# 1-RF-S.net
KiCad netlist of a schematic drawn in Altium Designer
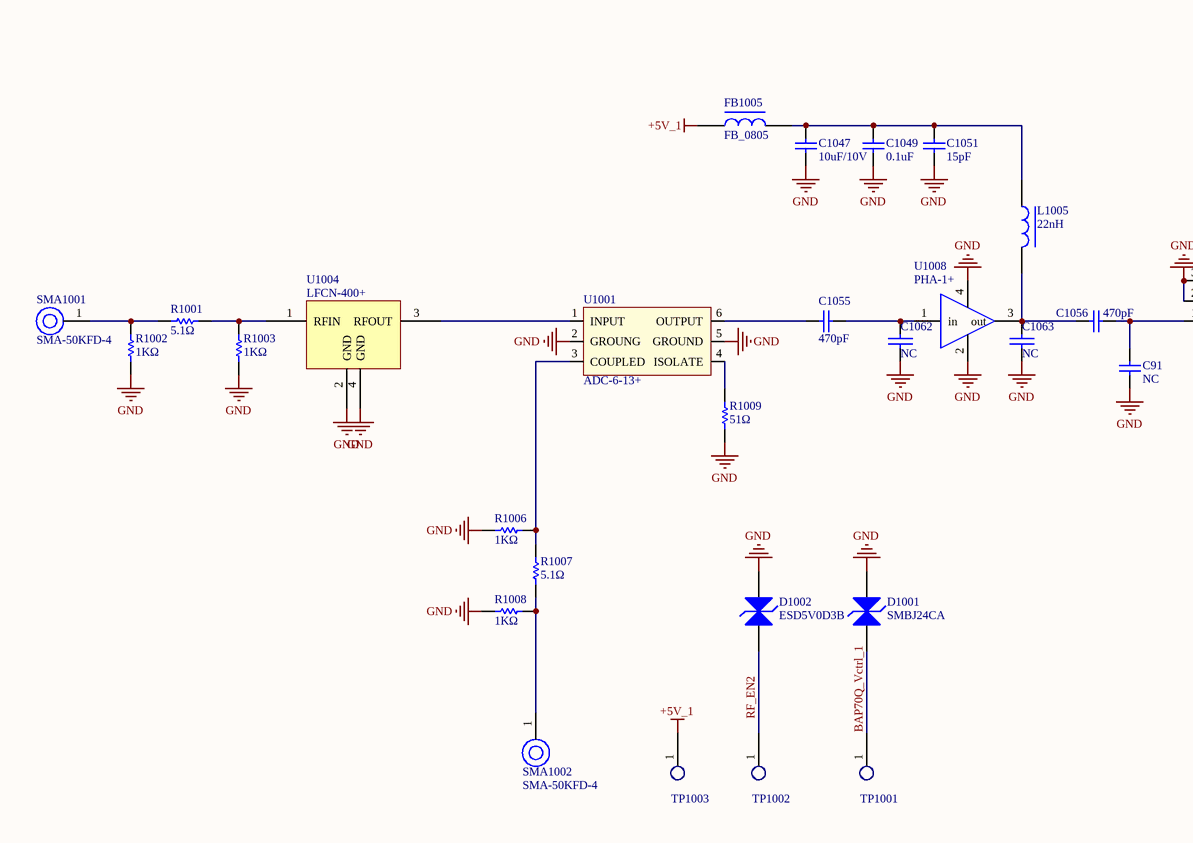
[diagram p0: 1-RF-S.SchDoc, left]
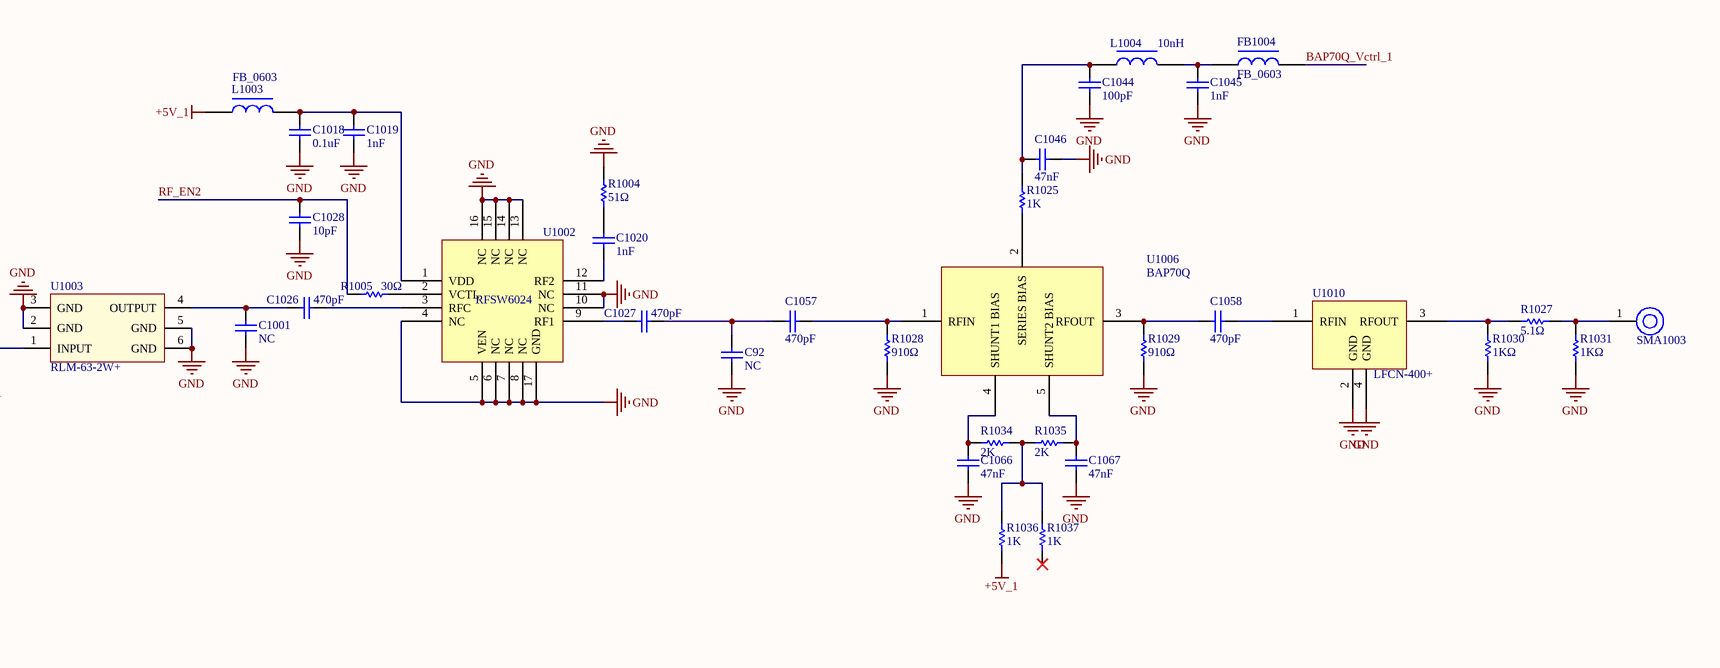
[diagram p1: 1-RF-S.SchDoc, right]

(export (version "E")
  (design (tool "Eeschema 10.0.6"))
  (components
    (comp (ref "C91")
      (value "NC")
      (footprint "C0805")
      (description "贴片电容_GRM215C1H100JA01D_10pF±5%,50V,0805")
      (libsource (lib "21贴片电容0805") (part "10pF贴片电容"))
    )
    (comp (ref "C92")
      (value "NC")
      (footprint "C0805")
      (description "贴片电容_GRM215C1H100JA01D_10pF±5%,50V,0805")
      (libsource (lib "21贴片电容0805") (part "10pF贴片电容"))
    )
    (comp (ref "C1001")
      (value "NC")
      (footprint "C0805")
      (description "贴片电容_GRM215C1H100JA01D_10pF±5%,50V,0805")
      (libsource (lib "21贴片电容0805") (part "10pF贴片电容"))
    )
    (comp (ref "C1018")
      (value "0.1uF")
      (footprint "C0603")
      (description "贴片电容_GRM188R71H104KA01D_0.1uF±10%,50V,0603")
      (libsource (lib "20贴片电容0603") (part "0.1uF贴片电容"))
    )
    (comp (ref "C1019")
      (value "1nF")
      (footprint "C0603")
      (description "贴片电容_GRM188R71H102KA01_1000pF±10%,50V,0603")
      (libsource (lib "20贴片电容0603") (part "1000pF贴片电容"))
    )
    (comp (ref "C1020")
      (value "1nF")
      (footprint "C0603")
      (description "贴片电容_GRM188R71H102KA01_1000pF±10%,50V,0603")
      (libsource (lib "20贴片电容0603") (part "1000pF贴片电容"))
    )
    (comp (ref "C1026")
      (value "470pF")
      (footprint "C0805")
      (description "贴片电容_GRM215C1H100JA01D_10pF±5%,50V,0805")
      (libsource (lib "21贴片电容0805") (part "10pF贴片电容"))
    )
    (comp (ref "C1027")
      (value "470pF")
      (footprint "C0805")
      (description "贴片电容_GRM215C1H100JA01D_10pF±5%,50V,0805")
      (libsource (lib "21贴片电容0805") (part "10pF贴片电容"))
    )
    (comp (ref "C1028")
      (value "10pF")
      (footprint "C0603")
      (description "贴片电容_0603CG100J500NT_10pF±5%,50V,0603")
      (libsource (lib "20贴片电容0603") (part "10pF贴片电容"))
    )
    (comp (ref "C1044")
      (value "100pF")
      (footprint "C0603")
      (description "贴片电容_GRM185C1H101K_100pF±10%,50V,0603")
      (libsource (lib "20贴片电容0603") (part "100pF贴片电容"))
    )
    (comp (ref "C1045")
      (value "1nF")
      (footprint "C0603")
      (description "贴片电容_GRM185C1H101K_100pF±10%,50V,0603")
      (libsource (lib "20贴片电容0603") (part "100pF贴片电容"))
    )
    (comp (ref "C1046")
      (value "47nF")
      (footprint "C0603")
      (description "贴片电容_GRM1885C1H473KA01D_47nF±10 %,50V,0603")
      (libsource (lib "20贴片电容0603") (part "47nF贴片电容"))
    )
    (comp (ref "C1047")
      (value "10uF/10V")
      (footprint "C0805")
      (description "贴片电容_GRM21BR61A106KE19L_10uF±10%,10V,0805")
      (libsource (lib "21贴片电容0805") (part "10uF贴片电容"))
    )
    (comp (ref "C1049")
      (value "0.1uF")
      (footprint "C0805")
      (description "贴片电容_GRM21BR71E104KA01L_100nF±10%,25V,0805")
      (libsource (lib "21贴片电容0805") (part "100nF贴片电容"))
    )
    (comp (ref "C1051")
      (value "15pF")
      (footprint "C0805")
      (description "贴片电容_GRM2165C1H150JA01D_15pF±5%,50V,0805")
      (libsource (lib "21贴片电容0805") (part "15pF贴片电容"))
    )
    (comp (ref "C1055")
      (value "470pF")
      (footprint "C0805")
      (description "贴片电容_GRM2165C1H1R0CA01D_1pF±0.25F,50V,0805")
      (libsource (lib "21贴片电容0805") (part "1pF贴片电容"))
    )
    (comp (ref "C1056")
      (value "470pF")
      (footprint "C0805")
      (description "贴片电容_GRM2165C1H3R0DD47D_3pF±0.5pF%,50V,0805")
      (libsource (lib "21贴片电容0805") (part "3pF贴片电容"))
    )
    (comp (ref "C1057")
      (value "470pF")
      (footprint "C0805")
      (description "贴片电容_GRM2165C1H101JA01D_100pF±5%,50V,0805")
      (libsource (lib "21贴片电容0805") (part "100pF贴片电容"))
    )
    (comp (ref "C1058")
      (value "470pF")
      (footprint "C0805")
      (description "贴片电容_GRM2165C1H101JA01D_100pF±5%,50V,0805")
      (libsource (lib "21贴片电容0805") (part "100pF贴片电容"))
    )
    (comp (ref "C1062")
      (value "NC")
      (footprint "C0805")
      (description "普通电容")
      (libsource (lib "27贴片电容DLC10D-0805") (part "DLC_0.5pF"))
    )
    (comp (ref "C1063")
      (value "NC")
      (footprint "C0805")
      (description "普通电容")
      (libsource (lib "27贴片电容DLC10D-0805") (part "DLC_0.5pF"))
    )
    (comp (ref "C1066")
      (value "47nF")
      (footprint "C0603")
      (description "贴片电容_GRM1885C1H473KA01D_47nF±10 %,50V,0603")
      (libsource (lib "20贴片电容0603") (part "47nF贴片电容"))
    )
    (comp (ref "C1067")
      (value "47nF")
      (footprint "C0603")
      (description "贴片电容_GRM1885C1H473KA01D_47nF±10 %,50V,0603")
      (libsource (lib "20贴片电容0603") (part "47nF贴片电容"))
    )
    (comp (ref "D1001")
      (value "SMBJ24CA")
      (footprint "DO-214AA")
      (description "TVS_SMBJ24CA_SMB封装")
      (libsource (lib "40二极管") (part "SMBJ12CA"))
    )
    (comp (ref "D1002")
      (value "ESD5V0D3B")
      (footprint "SOD-323")
      (description "ESD_ESD5V0D3B_SOD-323,5V,双管")
      (libsource (lib "40二极管") (part "ESD5B5.0ST1G"))
    )
    (comp (ref "FB1004")
      (value "FB_0603")
      (footprint "L0603")
      (description "贴片磁珠_100R,0603")
      (libsource (lib "32贴片磁珠0603") (part "0603贴片磁珠"))
    )
    (comp (ref "FB1005")
      (value "FB_0805")
      (footprint "L0805")
      (description "贴片磁珠_600R,0805")
      (libsource (lib "33贴片磁珠0805") (part "0805贴片磁珠"))
    )
    (comp (ref "L1003")
      (value "FB_0603")
      (footprint "L0603")
      (libsource (lib "33贴片磁珠0805") (part "0805贴片磁珠"))
    )
    (comp (ref "L1004")
      (value "10nH")
      (footprint "L0603")
      (description "贴片电感_3.3nH,0603")
      (libsource (lib "30贴片电感0603") (part "3.3nH贴片电感"))
    )
    (comp (ref "L1005")
      (value "22nH")
      (footprint "L0805")
      (description "贴片电感_22nH,0805")
      (libsource (lib "31贴片电感0805") (part "22nH贴片电感"))
    )
    (comp (ref "R1001")
      (value "5.1Ω")
      (footprint "R0805")
      (description "贴片电阻_0805,5.1Ω,±1％")
      (libsource (lib "11贴片电阻0805") (part "18Ω贴片电阻"))
    )
    (comp (ref "R1002")
      (value "1KΩ")
      (footprint "R0805")
      (description "贴片电阻_0805,1KΩ,±5％")
      (libsource (lib "11贴片电阻0805") (part "300Ω贴片电阻"))
    )
    (comp (ref "R1003")
      (value "1KΩ")
      (footprint "R0805")
      (description "贴片电阻_0805,1KΩ,±5％")
      (libsource (lib "11贴片电阻0805") (part "300Ω贴片电阻"))
    )
    (comp (ref "R1004")
      (value "51Ω")
      (footprint "R0603")
      (description "贴片电阻_51Ω±5%,0603")
      (libsource (lib "10贴片电阻0603") (part "51Ω贴片电阻"))
    )
    (comp (ref "R1005")
      (value "30Ω")
      (footprint "R0603")
      (description "贴片电阻_30Ω±5%,0603")
      (libsource (lib "10贴片电阻0603") (part "30Ω贴片电阻"))
    )
    (comp (ref "R1006")
      (value "1KΩ")
      (footprint "R0805")
      (description "贴片电阻_0805,1KΩ,±5％")
      (libsource (lib "11贴片电阻0805") (part "300Ω贴片电阻"))
    )
    (comp (ref "R1007")
      (value "5.1Ω")
      (footprint "R0805")
      (description "贴片电阻_0805,5.1Ω,±1％")
      (libsource (lib "11贴片电阻0805") (part "18Ω贴片电阻"))
    )
    (comp (ref "R1008")
      (value "1KΩ")
      (footprint "R0805")
      (description "贴片电阻_0805,1KΩ,±5％")
      (libsource (lib "11贴片电阻0805") (part "300Ω贴片电阻"))
    )
    (comp (ref "R1009")
      (value "51Ω")
      (footprint "R0805")
      (description "贴片电阻_51Ω±5%,0805")
      (libsource (lib "11贴片电阻0805") (part "51Ω贴片电阻"))
    )
    (comp (ref "R1025")
      (value "1K")
      (footprint "R0603")
      (description "贴片电阻_1K±5%,0603")
      (libsource (lib "10贴片电阻0603") (part "1K贴片电阻"))
    )
    (comp (ref "R1027")
      (value "5.1Ω")
      (footprint "R0805")
      (description "贴片电阻_0805,5.1Ω,±1％")
      (libsource (lib "11贴片电阻0805") (part "18Ω贴片电阻"))
    )
    (comp (ref "R1028")
      (value "910Ω")
      (footprint "R0805")
      (description "贴片电阻_910Ω±5%,0805")
      (libsource (lib "11贴片电阻0805") (part "910Ω贴片电阻"))
    )
    (comp (ref "R1029")
      (value "910Ω")
      (footprint "R0805")
      (description "贴片电阻_910Ω±5%,0805")
      (libsource (lib "11贴片电阻0805") (part "910Ω贴片电阻"))
    )
    (comp (ref "R1030")
      (value "1KΩ")
      (footprint "R0805")
      (description "贴片电阻_0805,1KΩ,±5％")
      (libsource (lib "11贴片电阻0805") (part "300Ω贴片电阻"))
    )
    (comp (ref "R1031")
      (value "1KΩ")
      (footprint "R0805")
      (description "贴片电阻_0805,1KΩ,±5％")
      (libsource (lib "11贴片电阻0805") (part "300Ω贴片电阻"))
    )
    (comp (ref "R1034")
      (value "2K")
      (footprint "R0603")
      (description "贴片电阻_2K±5%,0603")
      (libsource (lib "10贴片电阻0603") (part "2K贴片电阻"))
    )
    (comp (ref "R1035")
      (value "2K")
      (footprint "R0603")
      (description "贴片电阻_2K±5%,0603")
      (libsource (lib "10贴片电阻0603") (part "2K贴片电阻"))
    )
    (comp (ref "R1036")
      (value "1K")
      (footprint "R0603")
      (description "贴片电阻_1K±5%,0603")
      (libsource (lib "10贴片电阻0603") (part "1K贴片电阻"))
    )
    (comp (ref "R1037")
      (value "1K")
      (footprint "R0603")
      (description "贴片电阻_1K±5%,0603")
      (libsource (lib "10贴片电阻0603") (part "1K贴片电阻"))
    )
    (comp (ref "SMA1001")
      (value "SMA-50KFD-4")
      (footprint "SMA-50KFD-4")
      (description "射频同轴连接器_SMA-50KFD-4")
      (libsource (lib "90RF连接器") (part "SMA-50KFD-4"))
    )
    (comp (ref "SMA1002")
      (value "SMA-50KFD-4")
      (footprint "SMA-50KFD-4")
      (description "射频同轴连接器_SMA-50KFD-4")
      (libsource (lib "90RF连接器") (part "SMA-50KFD-4"))
    )
    (comp (ref "SMA1003")
      (value "SMA-50KFD-4")
      (footprint "SMA-50KFD-4")
      (description "射频同轴连接器_SMA-50KFD-4")
      (libsource (lib "90RF连接器") (part "SMA-50KFD-4"))
    )
    (comp (ref "TP1001")
      (value "TEST")
      (footprint "FC-M4")
      (description "表贴测试点1mm")
      (libsource (lib "92-其他（穿心电容，test等）") (part "TP1mm"))
    )
    (comp (ref "TP1002")
      (value "TEST")
      (footprint "FC-M4")
      (description "表贴测试点1mm")
      (libsource (lib "92-其他（穿心电容，test等）") (part "TP1mm"))
    )
    (comp (ref "TP1003")
      (value "TEST")
      (footprint "FC-M4")
      (description "表贴测试点1mm")
      (libsource (lib "92-其他（穿心电容，test等）") (part "TP1mm"))
    )
    (comp (ref "U1001")
      (value "ADC-6-13+")
      (footprint "6SM-2R54-7R87X5R59")
      (description "50Ω,5 to200MHz")
      (libsource (lib "105电桥&耦合器") (part "ADC-6-1R+"))
    )
    (comp (ref "U1002")
      (value "RFSW6024")
      (footprint "QFN16_0R65_4X4-1")
      (libsource (lib "80射频开关") (part "RFSW6124"))
    )
    (comp (ref "U1003")
      (value "RLM-63-2W+")
      (footprint "6SM-2R54-7R87X6R35")
      (description "50Ω,30 to6000MHz")
      (libsource (lib "106限幅器") (part "RLM-63-2W+"))
    )
    (comp (ref "U1004")
      (value "LFCN-400+")
      (footprint "LFCN-3216")
      (description "滤波器_LFCN-2500+_DC~2500MHz,3216")
      (libsource (lib "36滤波器") (part "LFCN-2500+"))
    )
    (comp (ref "U1006")
      (value "BAP70Q")
      (footprint "SOT23-5")
      (description "二极管衰减器_BAP70Q_300kHz ~4GHz,SOT753")
      (libsource (lib "75衰减器") (part "BAP70Q"))
    )
    (comp (ref "U1008")
      (value "PHA-1+")
      (footprint "SOT-89")
      (description "功率放大管_PHA-1+_0.05-6GHz,SOT89")
      (libsource (lib "73功率放大器") (part "PHA-1+"))
    )
    (comp (ref "U1010")
      (value "LFCN-400+")
      (footprint "LFCN-3216")
      (description "滤波器_LFCN-2500+_DC~2500MHz,3216")
      (libsource (lib "36滤波器") (part "LFCN-2500+"))
    )
  )
  (nets
    (net (code "1") (name "+5V_1") (class "Default")
      (node (ref "FB1005") (pin "1") (pinfunction "1_1") (pintype "passive"))
      (node (ref "L1003") (pin "1") (pinfunction "1_1") (pintype "passive"))
      (node (ref "R1036") (pin "1") (pinfunction "1_1") (pintype "passive"))
      (node (ref "TP1003") (pin "1") (pinfunction "TP_1") (pintype "passive"))
    )
    (net (code "2") (name "/BAP70Q_Vctrl_1") (class "Default")
      (node (ref "D1001") (pin "2") (pinfunction "2_2") (pintype "passive"))
      (node (ref "FB1004") (pin "2") (pinfunction "2_2") (pintype "passive"))
      (node (ref "TP1001") (pin "1") (pinfunction "TP_1") (pintype "passive"))
    )
    (net (code "3") (name "/RF_EN2") (class "Default")
      (node (ref "C1028") (pin "2") (pinfunction "2_2") (pintype "passive"))
      (node (ref "D1002") (pin "1") (pinfunction "1_1") (pintype "passive"))
      (node (ref "R1005") (pin "1") (pinfunction "1_1") (pintype "passive"))
      (node (ref "TP1002") (pin "1") (pinfunction "TP_1") (pintype "passive"))
    )
    (net (code "4") (name "GND") (class "Default")
      (node (ref "C1001") (pin "2") (pinfunction "2_2") (pintype "passive"))
      (node (ref "C1018") (pin "2") (pinfunction "2_2") (pintype "passive"))
      (node (ref "C1019") (pin "1") (pinfunction "1_1") (pintype "passive"))
      (node (ref "C1028") (pin "1") (pinfunction "1_1") (pintype "passive"))
      (node (ref "C1044") (pin "1") (pinfunction "1_1") (pintype "passive"))
      (node (ref "C1045") (pin "1") (pinfunction "1_1") (pintype "passive"))
      (node (ref "C1046") (pin "1") (pinfunction "1_1") (pintype "passive"))
      (node (ref "C1047") (pin "1") (pinfunction "1_1") (pintype "passive"))
      (node (ref "C1049") (pin "1") (pinfunction "1_1") (pintype "passive"))
      (node (ref "C1051") (pin "1") (pinfunction "1_1") (pintype "passive"))
      (node (ref "C1062") (pin "1") (pintype "passive"))
      (node (ref "C1063") (pin "1") (pintype "passive"))
      (node (ref "C1066") (pin "1") (pinfunction "1_1") (pintype "passive"))
      (node (ref "C1067") (pin "1") (pinfunction "1_1") (pintype "passive"))
      (node (ref "C91") (pin "2") (pinfunction "2_2") (pintype "passive"))
      (node (ref "C92") (pin "1") (pinfunction "1_1") (pintype "passive"))
      (node (ref "D1001") (pin "1") (pinfunction "1_1") (pintype "passive"))
      (node (ref "D1002") (pin "2") (pinfunction "2_2") (pintype "passive"))
      (node (ref "R1002") (pin "1") (pinfunction "1_1") (pintype "passive"))
      (node (ref "R1003") (pin "1") (pinfunction "1_1") (pintype "passive"))
      (node (ref "R1004") (pin "2") (pinfunction "2_2") (pintype "passive"))
      (node (ref "R1006") (pin "1") (pinfunction "1_1") (pintype "passive"))
      (node (ref "R1008") (pin "1") (pinfunction "1_1") (pintype "passive"))
      (node (ref "R1009") (pin "2") (pinfunction "2_2") (pintype "passive"))
      (node (ref "R1028") (pin "1") (pinfunction "1_1") (pintype "passive"))
      (node (ref "R1029") (pin "1") (pinfunction "1_1") (pintype "passive"))
      (node (ref "R1030") (pin "1") (pinfunction "1_1") (pintype "passive"))
      (node (ref "R1031") (pin "1") (pinfunction "1_1") (pintype "passive"))
      (node (ref "U1001") (pin "2") (pinfunction "GROUNG_2") (pintype "passive"))
      (node (ref "U1001") (pin "5") (pinfunction "GROUND_5") (pintype "passive"))
      (node (ref "U1002") (pin "10") (pinfunction "NC_10") (pintype "passive"))
      (node (ref "U1002") (pin "11") (pinfunction "NC_11") (pintype "passive"))
      (node (ref "U1002") (pin "13") (pinfunction "NC_13") (pintype "passive"))
      (node (ref "U1002") (pin "14") (pinfunction "NC_14") (pintype "passive"))
      (node (ref "U1002") (pin "15") (pinfunction "NC_15") (pintype "passive"))
      (node (ref "U1002") (pin "16") (pinfunction "NC_16") (pintype "passive"))
      (node (ref "U1002") (pin "17") (pinfunction "GND_17") (pintype "passive"))
      (node (ref "U1002") (pin "4") (pinfunction "NC_4") (pintype "passive"))
      (node (ref "U1002") (pin "5") (pinfunction "VEN_5") (pintype "passive"))
      (node (ref "U1002") (pin "6") (pinfunction "NC_6") (pintype "passive"))
      (node (ref "U1002") (pin "7") (pinfunction "NC_7") (pintype "passive"))
      (node (ref "U1002") (pin "8") (pinfunction "NC_8") (pintype "passive"))
      (node (ref "U1003") (pin "2") (pinfunction "GND_2") (pintype "passive"))
      (node (ref "U1003") (pin "3") (pinfunction "GND_3") (pintype "passive"))
      (node (ref "U1003") (pin "5") (pinfunction "GND_5") (pintype "passive"))
      (node (ref "U1003") (pin "6") (pinfunction "GND_6") (pintype "passive"))
      (node (ref "U1004") (pin "2") (pinfunction "GND_2") (pintype "passive"))
      (node (ref "U1004") (pin "4") (pinfunction "GND_4") (pintype "passive"))
      (node (ref "U1008") (pin "2") (pinfunction "2_2") (pintype "passive"))
      (node (ref "U1008") (pin "4") (pinfunction "4_4") (pintype "passive"))
      (node (ref "U1010") (pin "2") (pinfunction "GND_2") (pintype "passive"))
      (node (ref "U1010") (pin "4") (pinfunction "GND_4") (pintype "passive"))
    )
    (net (code "5") (name "Net-(C1020-Pad2)") (class "Default")
      (node (ref "C1020") (pin "2") (pinfunction "2_2") (pintype "passive"))
      (node (ref "R1004") (pin "1") (pinfunction "1_1") (pintype "passive"))
    )
    (net (code "6") (name "Net-(C1027-Pad2)") (class "Default")
      (node (ref "C1027") (pin "2") (pinfunction "2_2") (pintype "passive"))
      (node (ref "C1057") (pin "1") (pinfunction "1_1") (pintype "passive"))
      (node (ref "C92") (pin "2") (pinfunction "2_2") (pintype "passive"))
    )
    (net (code "7") (name "Net-(C1044-Pad2)") (class "Default")
      (node (ref "C1044") (pin "2") (pinfunction "2_2") (pintype "passive"))
      (node (ref "C1046") (pin "2") (pinfunction "2_2") (pintype "passive"))
      (node (ref "L1004") (pin "1") (pinfunction "1_1") (pintype "passive"))
      (node (ref "R1025") (pin "2") (pinfunction "2_2") (pintype "passive"))
    )
    (net (code "8") (name "Net-(C1045-Pad2)") (class "Default")
      (node (ref "C1045") (pin "2") (pinfunction "2_2") (pintype "passive"))
      (node (ref "FB1004") (pin "1") (pinfunction "1_1") (pintype "passive"))
      (node (ref "L1004") (pin "2") (pinfunction "2_2") (pintype "passive"))
    )
    (net (code "9") (name "Net-(C1047-Pad2)") (class "Default")
      (node (ref "C1047") (pin "2") (pinfunction "2_2") (pintype "passive"))
      (node (ref "C1049") (pin "2") (pinfunction "2_2") (pintype "passive"))
      (node (ref "C1051") (pin "2") (pinfunction "2_2") (pintype "passive"))
      (node (ref "FB1005") (pin "2") (pinfunction "2_2") (pintype "passive"))
      (node (ref "L1005") (pin "1") (pinfunction "1_1") (pintype "passive"))
    )
    (net (code "10") (name "Net-(R1034-Pad2)") (class "Default")
      (node (ref "R1034") (pin "2") (pinfunction "2_2") (pintype "passive"))
      (node (ref "R1035") (pin "1") (pinfunction "1_1") (pintype "passive"))
      (node (ref "R1036") (pin "2") (pinfunction "2_2") (pintype "passive"))
      (node (ref "R1037") (pin "2") (pinfunction "2_2") (pintype "passive"))
    )
    (net (code "11") (name "Net-(SMA1001-Sig)") (class "Default")
      (node (ref "R1001") (pin "1") (pinfunction "1_1") (pintype "passive"))
      (node (ref "R1002") (pin "2") (pinfunction "2_2") (pintype "passive"))
      (node (ref "SMA1001") (pin "1") (pinfunction "Sig_1") (pintype "passive"))
    )
    (net (code "12") (name "Net-(SMA1002-Sig)") (class "Default")
      (node (ref "R1007") (pin "2") (pinfunction "2_2") (pintype "passive"))
      (node (ref "R1008") (pin "2") (pinfunction "2_2") (pintype "passive"))
      (node (ref "SMA1002") (pin "1") (pinfunction "Sig_1") (pintype "passive"))
    )
    (net (code "13") (name "Net-(SMA1003-Sig)") (class "Default")
      (node (ref "R1027") (pin "2") (pinfunction "2_2") (pintype "passive"))
      (node (ref "R1031") (pin "2") (pinfunction "2_2") (pintype "passive"))
      (node (ref "SMA1003") (pin "1") (pinfunction "Sig_1") (pintype "passive"))
    )
    (net (code "14") (name "Net-(U1001-COUPLED)") (class "Default")
      (node (ref "R1006") (pin "2") (pinfunction "2_2") (pintype "passive"))
      (node (ref "R1007") (pin "1") (pinfunction "1_1") (pintype "passive"))
      (node (ref "U1001") (pin "3") (pinfunction "COUPLED_3") (pintype "passive"))
    )
    (net (code "15") (name "Net-(U1001-INPUT)") (class "Default")
      (node (ref "U1001") (pin "1") (pinfunction "INPUT_1") (pintype "passive"))
      (node (ref "U1004") (pin "3") (pinfunction "RFOUT_3") (pintype "passive"))
    )
    (net (code "16") (name "Net-(U1001-ISOLATE)") (class "Default")
      (node (ref "R1009") (pin "1") (pinfunction "1_1") (pintype "passive"))
      (node (ref "U1001") (pin "4") (pinfunction "ISOLATE_4") (pintype "passive"))
    )
    (net (code "17") (name "Net-(U1001-OUTPUT)") (class "Default")
      (node (ref "C1055") (pin "1") (pinfunction "1_1") (pintype "passive"))
      (node (ref "U1001") (pin "6") (pinfunction "OUTPUT_6") (pintype "passive"))
    )
    (net (code "18") (name "Net-(U1002-RF1)") (class "Default")
      (node (ref "C1027") (pin "1") (pinfunction "1_1") (pintype "passive"))
      (node (ref "U1002") (pin "9") (pinfunction "RF1_9") (pintype "passive"))
    )
    (net (code "19") (name "Net-(U1002-RF2)") (class "Default")
      (node (ref "C1020") (pin "1") (pinfunction "1_1") (pintype "passive"))
      (node (ref "U1002") (pin "12") (pinfunction "RF2_12") (pintype "passive"))
    )
    (net (code "20") (name "Net-(U1002-RFC)") (class "Default")
      (node (ref "C1026") (pin "2") (pinfunction "2_2") (pintype "passive"))
      (node (ref "U1002") (pin "3") (pinfunction "RFC_3") (pintype "passive"))
    )
    (net (code "21") (name "Net-(U1002-VCTL)") (class "Default")
      (node (ref "R1005") (pin "2") (pinfunction "2_2") (pintype "passive"))
      (node (ref "U1002") (pin "2") (pinfunction "VCTL_2") (pintype "passive"))
    )
    (net (code "22") (name "Net-(U1002-VDD)") (class "Default")
      (node (ref "C1018") (pin "1") (pinfunction "1_1") (pintype "passive"))
      (node (ref "C1019") (pin "2") (pinfunction "2_2") (pintype "passive"))
      (node (ref "L1003") (pin "2") (pinfunction "2_2") (pintype "passive"))
      (node (ref "U1002") (pin "1") (pinfunction "VDD_1") (pintype "passive"))
    )
    (net (code "23") (name "Net-(U1003-INPUT)") (class "Default")
      (node (ref "C1056") (pin "2") (pinfunction "2_2") (pintype "passive"))
      (node (ref "C91") (pin "1") (pinfunction "1_1") (pintype "passive"))
      (node (ref "U1003") (pin "1") (pinfunction "INPUT_1") (pintype "passive"))
    )
    (net (code "24") (name "Net-(U1003-OUTPUT)") (class "Default")
      (node (ref "C1001") (pin "1") (pinfunction "1_1") (pintype "passive"))
      (node (ref "C1026") (pin "1") (pinfunction "1_1") (pintype "passive"))
      (node (ref "U1003") (pin "4") (pinfunction "OUTPUT_4") (pintype "passive"))
    )
    (net (code "25") (name "Net-(U1004-RFIN)") (class "Default")
      (node (ref "R1001") (pin "2") (pinfunction "2_2") (pintype "passive"))
      (node (ref "R1003") (pin "2") (pinfunction "2_2") (pintype "passive"))
      (node (ref "U1004") (pin "1") (pinfunction "RFIN_1") (pintype "passive"))
    )
    (net (code "26") (name "Net-(U1006-RFIN)") (class "Default")
      (node (ref "C1057") (pin "2") (pinfunction "2_2") (pintype "passive"))
      (node (ref "R1028") (pin "2") (pinfunction "2_2") (pintype "passive"))
      (node (ref "U1006") (pin "1") (pinfunction "RFIN_1") (pintype "passive"))
    )
    (net (code "27") (name "Net-(U1006-RFOUT)") (class "Default")
      (node (ref "C1058") (pin "1") (pinfunction "1_1") (pintype "passive"))
      (node (ref "R1029") (pin "2") (pinfunction "2_2") (pintype "passive"))
      (node (ref "U1006") (pin "3") (pinfunction "RFOUT_3") (pintype "passive"))
    )
    (net (code "28") (name "Net-(U1006-SERIES_BIAS)") (class "Default")
      (node (ref "R1025") (pin "1") (pinfunction "1_1") (pintype "passive"))
      (node (ref "U1006") (pin "2") (pinfunction "SERIES_BIAS_2") (pintype "passive"))
    )
    (net (code "29") (name "Net-(U1006-SHUNT1_BIAS)") (class "Default")
      (node (ref "C1066") (pin "2") (pinfunction "2_2") (pintype "passive"))
      (node (ref "R1034") (pin "1") (pinfunction "1_1") (pintype "passive"))
      (node (ref "U1006") (pin "4") (pinfunction "SHUNT1_BIAS_4") (pintype "passive"))
    )
    (net (code "30") (name "Net-(U1006-SHUNT2_BIAS)") (class "Default")
      (node (ref "C1067") (pin "2") (pinfunction "2_2") (pintype "passive"))
      (node (ref "R1035") (pin "2") (pinfunction "2_2") (pintype "passive"))
      (node (ref "U1006") (pin "5") (pinfunction "SHUNT2_BIAS_5") (pintype "passive"))
    )
    (net (code "31") (name "Net-(U1008-in)") (class "Default")
      (node (ref "C1055") (pin "2") (pinfunction "2_2") (pintype "passive"))
      (node (ref "C1062") (pin "2") (pintype "passive"))
      (node (ref "U1008") (pin "1") (pinfunction "in_1") (pintype "passive"))
    )
    (net (code "32") (name "Net-(U1008-out)") (class "Default")
      (node (ref "C1056") (pin "1") (pinfunction "1_1") (pintype "passive"))
      (node (ref "C1063") (pin "2") (pintype "passive"))
      (node (ref "L1005") (pin "2") (pinfunction "2_2") (pintype "passive"))
      (node (ref "U1008") (pin "3") (pinfunction "out_3") (pintype "passive"))
    )
    (net (code "33") (name "Net-(U1010-RFIN)") (class "Default")
      (node (ref "C1058") (pin "2") (pinfunction "2_2") (pintype "passive"))
      (node (ref "U1010") (pin "1") (pinfunction "RFIN_1") (pintype "passive"))
    )
    (net (code "34") (name "Net-(U1010-RFOUT)") (class "Default")
      (node (ref "R1027") (pin "1") (pinfunction "1_1") (pintype "passive"))
      (node (ref "R1030") (pin "2") (pinfunction "2_2") (pintype "passive"))
      (node (ref "U1010") (pin "3") (pinfunction "RFOUT_3") (pintype "passive"))
    )
    (net (code "35") (name "unconnected-(R1037-Pad1)") (class "Default")
      (node (ref "R1037") (pin "1") (pinfunction "1_1") (pintype "passive+no_connect"))
    )
  )
)
